# UOF_proto_2V4.net
KiCad netlist of a schematic drawn in EAGLE
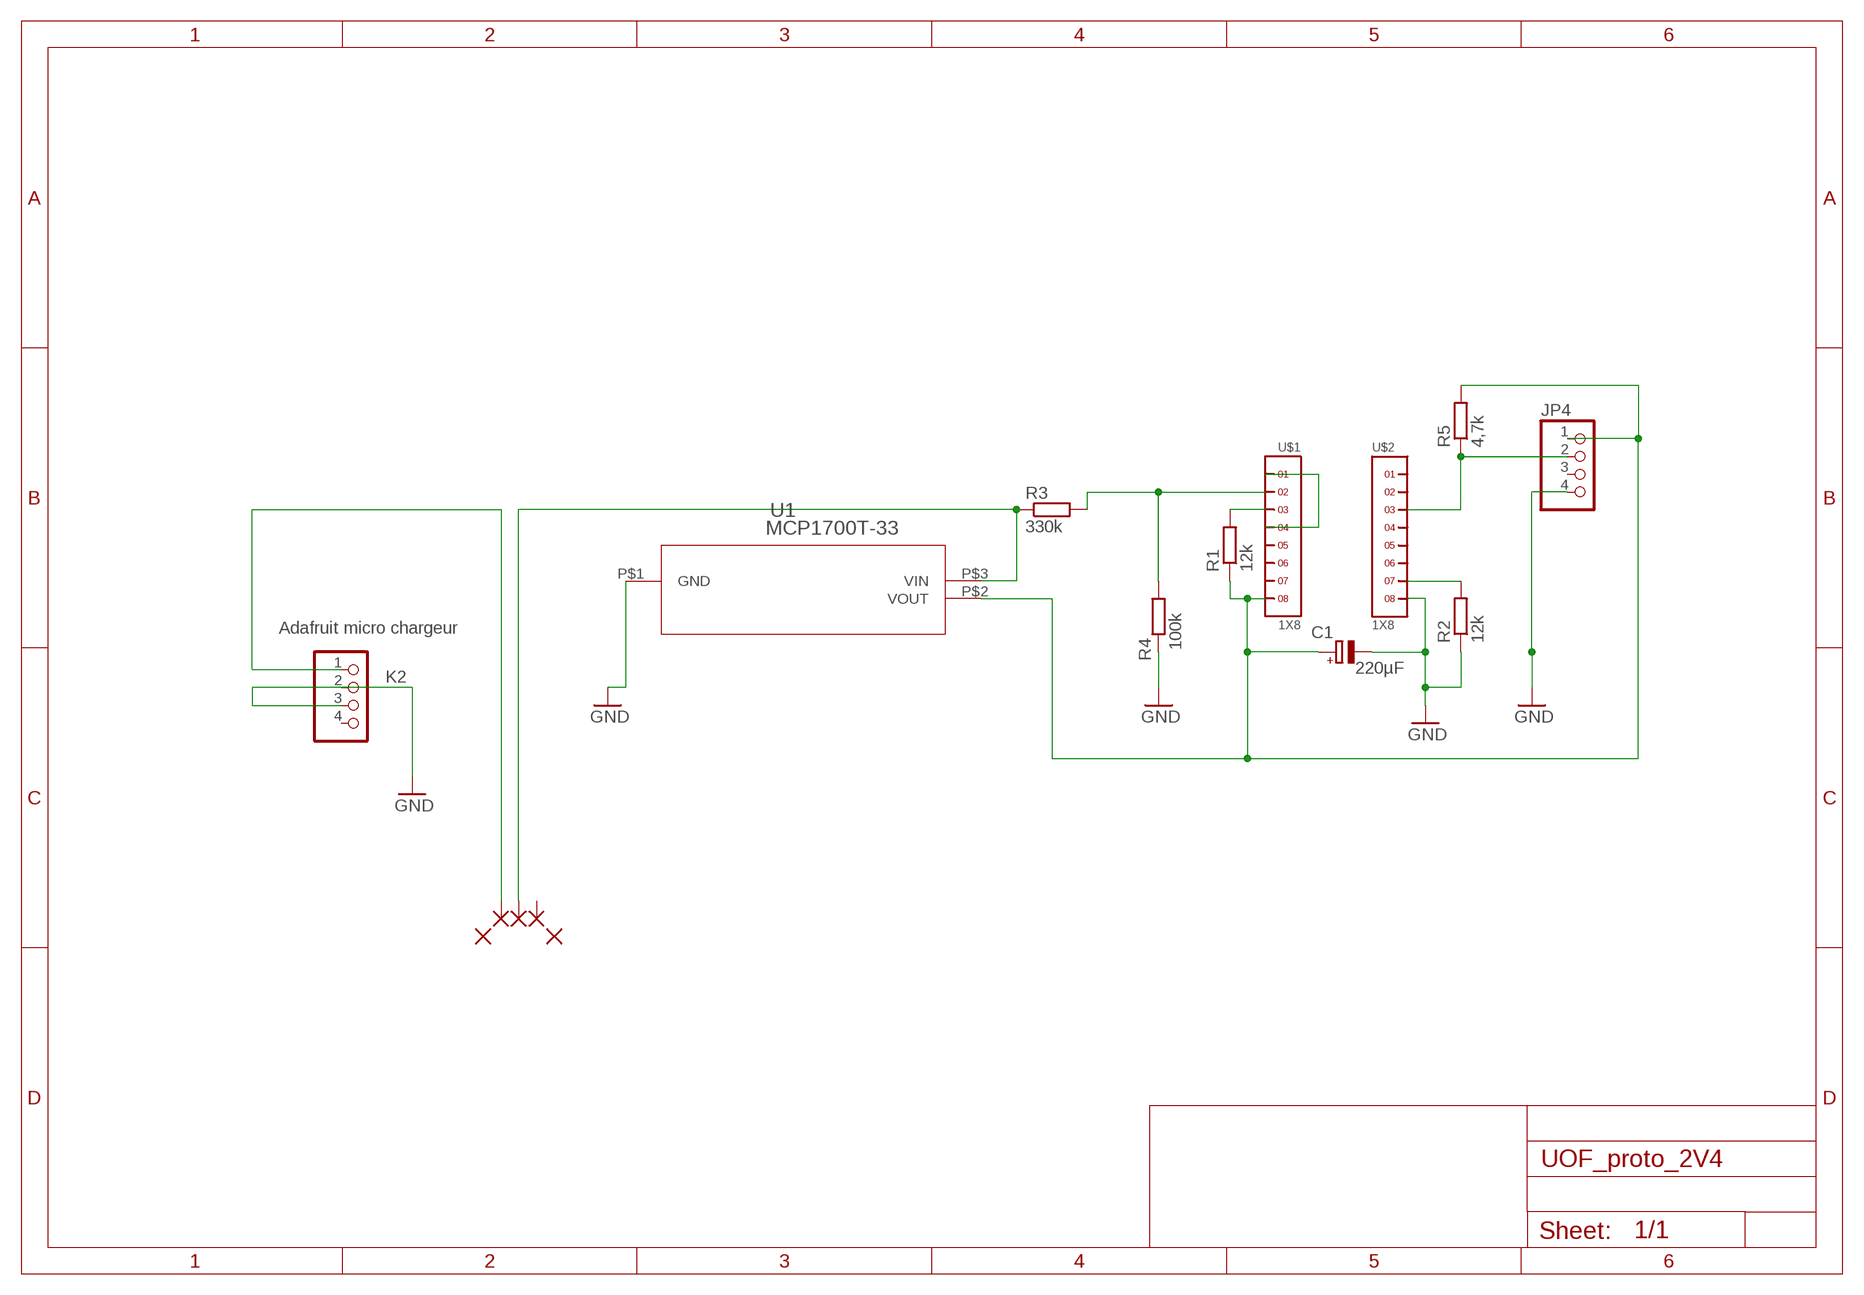
[diagram p0: schematic, sheet 1]

(export (version "E")
  (design (tool "Eeschema 10.0.6"))
  (components
    (comp (ref "C1")
      (value "220µF")
      (footprint "eagle-import:E5-10,5")
      (libsource (lib "eagle-import") (part "CPOL-EUE5-10.5"))
    )
    (comp (ref "JP4")
      (value "PINHD-1X4")
      (footprint "eagle-import:1X04")
      (libsource (lib "eagle-import") (part "PINHD-1X4"))
    )
    (comp (ref "K2")
      (value "Adafruit micro chargeur")
      (footprint "eagle-import:1X04")
      (libsource (lib "eagle-import") (part "pinhead_325_PINHD-1X4"))
    )
    (comp (ref "PAD1")
      (value "1,6/0,8")
      (footprint "eagle-import:1,6_0,8")
      (libsource (lib "eagle-import") (part "1,6/0,8"))
    )
    (comp (ref "PAD2")
      (value "1,6/0,8")
      (footprint "eagle-import:1,6_0,8")
      (libsource (lib "eagle-import") (part "1,6/0,8"))
    )
    (comp (ref "PAD3")
      (value "1,6/0,8")
      (footprint "eagle-import:1,6_0,8")
      (libsource (lib "eagle-import") (part "1,6/0,8"))
    )
    (comp (ref "PAD4")
      (value "N_2,0/1,5")
      (footprint "eagle-import:2,0_1,5")
      (libsource (lib "eagle-import") (part "N_2,0/1,5"))
    )
    (comp (ref "PAD5")
      (value "N_2,0/1,5")
      (footprint "eagle-import:2,0_1,5")
      (libsource (lib "eagle-import") (part "N_2,0/1,5"))
    )
    (comp (ref "R1")
      (value "12k")
      (footprint "eagle-import:0207_10")
      (libsource (lib "eagle-import") (part "R-EU_0207/10"))
    )
    (comp (ref "R2")
      (value "12k")
      (footprint "eagle-import:0207_10")
      (libsource (lib "eagle-import") (part "R-EU_0207/10"))
    )
    (comp (ref "R3")
      (value "330k")
      (footprint "eagle-import:0207_10")
      (libsource (lib "eagle-import") (part "R-EU_0207/10"))
    )
    (comp (ref "R4")
      (value "100k")
      (footprint "eagle-import:0207_10")
      (libsource (lib "eagle-import") (part "R-EU_0207/10"))
    )
    (comp (ref "R5")
      (value "4,7k")
      (footprint "eagle-import:0204V")
      (libsource (lib "eagle-import") (part "R-EU_0204/2V"))
    )
    (comp (ref "U$1")
      (value "1X8")
      (footprint "eagle-import:1X8")
      (libsource (lib "eagle-import") (part "1X8"))
    )
    (comp (ref "U$2")
      (value "1X8")
      (footprint "eagle-import:1X8")
      (libsource (lib "eagle-import") (part "1X8"))
    )
    (comp (ref "U1")
      (value "MCP1700T-33")
      (footprint "eagle-import:SOT-23")
      (libsource (lib "eagle-import") (part "MCP1700T-3302E/TTSOT-23"))
    )
  )
  (nets
    (net (code "1") (name "GND") (class "Default")
      (node (ref "C1") (pin "-") (pinfunction "-_-") (pintype "passive"))
      (node (ref "JP4") (pin "4") (pinfunction "4_4") (pintype "passive"))
      (node (ref "K2") (pin "2") (pinfunction "2_2") (pintype "passive"))
      (node (ref "K2") (pin "3") (pinfunction "3_3") (pintype "passive"))
      (node (ref "R2") (pin "1") (pinfunction "1_1") (pintype "passive"))
      (node (ref "R4") (pin "2") (pinfunction "2_2") (pintype "passive"))
      (node (ref "U$2") (pin "8") (pinfunction "8_8") (pintype "bidirectional"))
      (node (ref "U1") (pin "P$1") (pinfunction "GND_P$1") (pintype "passive"))
    )
    (net (code "2") (name "Net-(JP4-Pad2)") (class "Default")
      (node (ref "JP4") (pin "2") (pinfunction "2_2") (pintype "passive"))
      (node (ref "R5") (pin "1") (pinfunction "1_1") (pintype "passive"))
      (node (ref "U$2") (pin "3") (pinfunction "3_3") (pintype "bidirectional"))
    )
    (net (code "3") (name "Net-(PAD1-P)") (class "Default")
      (node (ref "K2") (pin "1") (pinfunction "1_1") (pintype "passive"))
      (node (ref "PAD1") (pin "1") (pinfunction "P_1") (pintype "passive"))
    )
    (net (code "4") (name "Net-(PAD2-P)") (class "Default")
      (node (ref "PAD2") (pin "1") (pinfunction "P_1") (pintype "passive"))
      (node (ref "R3") (pin "1") (pinfunction "1_1") (pintype "passive"))
      (node (ref "U1") (pin "P$3") (pinfunction "VIN_P$3") (pintype "passive"))
    )
    (net (code "5") (name "Net-(R1-Pad2)") (class "Default")
      (node (ref "R1") (pin "2") (pinfunction "2_2") (pintype "passive"))
      (node (ref "U$1") (pin "3") (pinfunction "3_3") (pintype "bidirectional"))
    )
    (net (code "6") (name "Net-(R2-Pad2)") (class "Default")
      (node (ref "R2") (pin "2") (pinfunction "2_2") (pintype "passive"))
      (node (ref "U$2") (pin "7") (pinfunction "7_7") (pintype "bidirectional"))
    )
    (net (code "7") (name "Net-(R3-Pad2)") (class "Default")
      (node (ref "R3") (pin "2") (pinfunction "2_2") (pintype "passive"))
      (node (ref "R4") (pin "1") (pinfunction "1_1") (pintype "passive"))
      (node (ref "U$1") (pin "2") (pinfunction "2_2") (pintype "bidirectional"))
    )
    (net (code "8") (name "Net-(U$1-Pad1)") (class "Default")
      (node (ref "U$1") (pin "1") (pinfunction "1_1") (pintype "bidirectional"))
      (node (ref "U$1") (pin "4") (pinfunction "4_4") (pintype "bidirectional"))
    )
    (net (code "9") (name "Net-(U1-VOUT)") (class "Default")
      (node (ref "C1") (pin "+") (pinfunction "+_+") (pintype "passive"))
      (node (ref "JP4") (pin "1") (pinfunction "1_1") (pintype "passive"))
      (node (ref "R1") (pin "1") (pinfunction "1_1") (pintype "passive"))
      (node (ref "R5") (pin "2") (pinfunction "2_2") (pintype "passive"))
      (node (ref "U$1") (pin "8") (pinfunction "8_8") (pintype "bidirectional"))
      (node (ref "U1") (pin "P$2") (pinfunction "VOUT_P$2") (pintype "passive"))
    )
    (net (code "10") (name "unconnected-(JP4-Pad3)") (class "Default")
      (node (ref "JP4") (pin "3") (pinfunction "3_3") (pintype "passive"))
    )
    (net (code "11") (name "unconnected-(K2-Pad4)") (class "Default")
      (node (ref "K2") (pin "4") (pinfunction "4_4") (pintype "passive"))
    )
    (net (code "12") (name "unconnected-(PAD3-P-Pad1)") (class "Default")
      (node (ref "PAD3") (pin "1") (pinfunction "P_1") (pintype "passive"))
    )
    (net (code "13") (name "unconnected-(U$1-Pad5)") (class "Default")
      (node (ref "U$1") (pin "5") (pinfunction "5_5") (pintype "bidirectional"))
    )
    (net (code "14") (name "unconnected-(U$1-Pad6)") (class "Default")
      (node (ref "U$1") (pin "6") (pinfunction "6_6") (pintype "bidirectional"))
    )
    (net (code "15") (name "unconnected-(U$1-Pad7)") (class "Default")
      (node (ref "U$1") (pin "7") (pinfunction "7_7") (pintype "bidirectional"))
    )
    (net (code "16") (name "unconnected-(U$2-Pad1)") (class "Default")
      (node (ref "U$2") (pin "1") (pinfunction "1_1") (pintype "bidirectional"))
    )
    (net (code "17") (name "unconnected-(U$2-Pad2)") (class "Default")
      (node (ref "U$2") (pin "2") (pinfunction "2_2") (pintype "bidirectional"))
    )
    (net (code "18") (name "unconnected-(U$2-Pad4)") (class "Default")
      (node (ref "U$2") (pin "4") (pinfunction "4_4") (pintype "bidirectional"))
    )
    (net (code "19") (name "unconnected-(U$2-Pad5)") (class "Default")
      (node (ref "U$2") (pin "5") (pinfunction "5_5") (pintype "bidirectional"))
    )
    (net (code "20") (name "unconnected-(U$2-Pad6)") (class "Default")
      (node (ref "U$2") (pin "6") (pinfunction "6_6") (pintype "bidirectional"))
    )
  )
)
